# MeasureBlock.net
KiCad netlist of a schematic drawn in Altium Designer
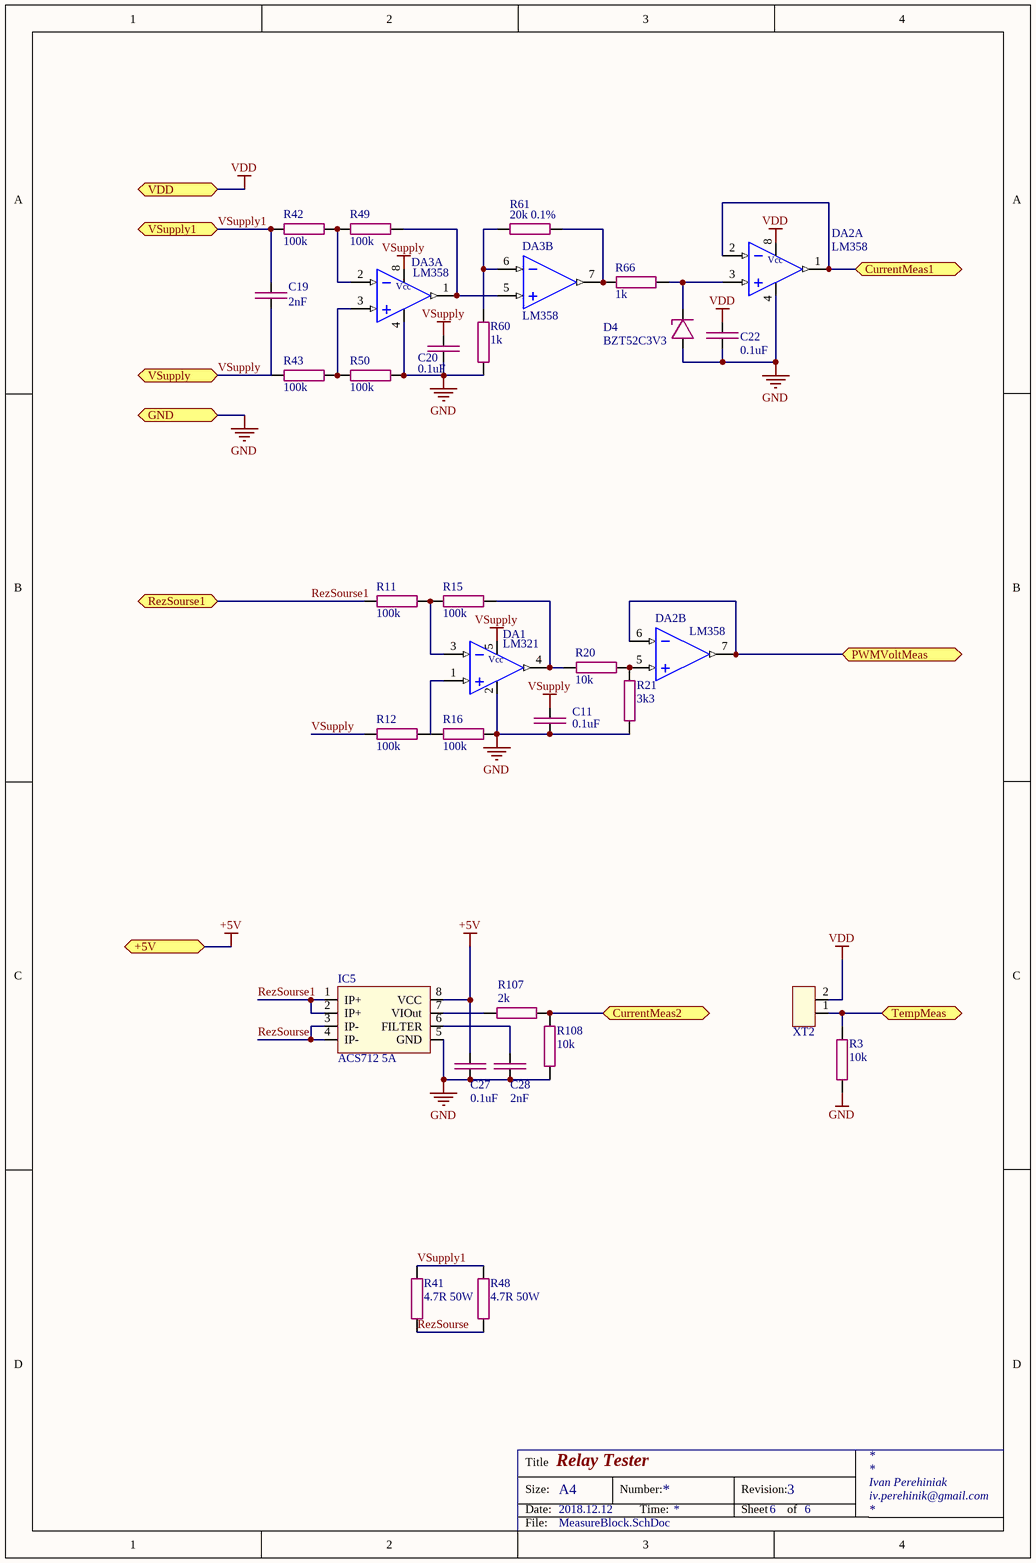
[diagram p0: MeasureBlock.SchDoc]

(export (version "E")
  (design (tool "Eeschema 10.0.6"))
  (components
    (comp (ref "C11")
      (value "0.1uF")
      (footprint "PcbLib:C0603")
      (description "CAP CER 0.1UF 50V X7R 0603")
      (fields (field (name "MANUFACTURER PART NUMBER") "GMK316F475ZG-T"))
      (libsource (lib "RCU") (part "GMK316F475ZG-T"))
    )
    (comp (ref "C19")
      (value "2nF")
      (footprint "PcbLib:C0603")
      (description "CAP CER 2000PF 50V X7R 0603")
      (fields (field (name "MANUFACTURER PART NUMBER") "CL10B202KB8NNNC"))
      (libsource (lib "RCU") (part "CL10B202KB8NNNC"))
    )
    (comp (ref "C20")
      (value "0.1uF")
      (footprint "PcbLib:C0603")
      (description "CAP CER 0.1UF 50V X7R 0603")
      (fields (field (name "MANUFACTURER PART NUMBER") "GMK316F475ZG-T"))
      (libsource (lib "RCU") (part "GMK316F475ZG-T"))
    )
    (comp (ref "C22")
      (value "0.1uF")
      (footprint "PcbLib:C0603")
      (description "CAP CER 0.1UF 50V X7R 0603")
      (fields (field (name "MANUFACTURER PART NUMBER") "GMK316F475ZG-T"))
      (libsource (lib "RCU") (part "GMK316F475ZG-T"))
    )
    (comp (ref "C27")
      (value "0.1uF")
      (footprint "PcbLib:C0603")
      (description "CAP CER 0.1UF 50V X7R 0603")
      (fields (field (name "MANUFACTURER PART NUMBER") "GMK316F475ZG-T"))
      (libsource (lib "RCU") (part "GMK316F475ZG-T"))
    )
    (comp (ref "C28")
      (value "2nF")
      (footprint "PcbLib:C0603")
      (description "CAP CER 2000PF 50V X7R 0603")
      (fields (field (name "MANUFACTURER PART NUMBER") "CL10B202KB8NNNC"))
      (libsource (lib "RCU") (part "CL10B202KB8NNNC"))
    )
    (comp (ref "D4")
      (value "BZT52C3V3")
      (footprint "PcbLib:SOD123")
      (description "Diode Zener Single 3.3V 6% 370mW 2-Pin SOD-123 T/R")
      (fields (field (name "MANUFACTURER PART NUMBER") "BZT52C3V3-7-F"))
      (libsource (lib "RCU") (part "BZT52C3V3-7-F"))
    )
    (comp (ref "DA1")
      (value "LM321")
      (footprint "PcbLib:SOT23-5")
      (description "IC OPAMP GP 1.3MHZ RRO SOT23-5")
      (fields (field (name "MANUFACTURER PART NUMBER") "LMV321ILT"))
      (libsource (lib "RCU") (part "LM321"))
    )
    (comp (ref "DA2")
      (value "LM358")
      (footprint "PcbLib:SOIC_N")
      (description "Dual IC OPAMP GP 1.1MHZ 8SO")
      (fields (field (name "MANUFACTURER PART NUMBER") "LM358DT"))
      (libsource (lib "RCU") (part "LM358DT"))
    )
    (comp (ref "DA3")
      (value "LM358")
      (footprint "PcbLib:SOIC_N")
      (description "Dual IC OPAMP GP 1.1MHZ 8SO")
      (fields (field (name "MANUFACTURER PART NUMBER") "LM358DT"))
      (libsource (lib "RCU") (part "LM358DT"))
    )
    (comp (ref "IC5")
      (value "ACS712 5A")
      (footprint "PcbLib:SOIC_N")
      (description "SENSOR CURRENT HALL 5A AC/DC")
      (fields (field (name "MANUFACTURER PART NUMBER") "ACS712ELCTR-05B-T"))
      (libsource (lib "RCU") (part "ACS712ELCTR-05B"))
    )
    (comp (ref "R3")
      (value "10k")
      (footprint "PcbLib:R0603")
      (description "RES SMD 10K OHM 1% 1/10W 0603")
      (fields (field (name "MANUFACTURER PART NUMBER") "CRCW060310K0FKTABC"))
      (libsource (lib "RCU") (part "CRCW060310K0FKTABC"))
    )
    (comp (ref "R11")
      (value "100k")
      (footprint "PcbLib:R0603")
      (description "RES SMD 100K OHM 5% 1/10W 0603")
      (fields (field (name "MANUFACTURER PART NUMBER") "ERJ-S03J104V"))
      (libsource (lib "RCU") (part "ERJ-S03J104V"))
    )
    (comp (ref "R12")
      (value "100k")
      (footprint "PcbLib:R0603")
      (description "RES SMD 100K OHM 5% 1/10W 0603")
      (fields (field (name "MANUFACTURER PART NUMBER") "ERJ-S03J104V"))
      (libsource (lib "RCU") (part "ERJ-S03J104V"))
    )
    (comp (ref "R15")
      (value "100k")
      (footprint "PcbLib:R0603")
      (description "RES SMD 100K OHM 5% 1/10W 0603")
      (fields (field (name "MANUFACTURER PART NUMBER") "ERJ-S03J104V"))
      (libsource (lib "RCU") (part "ERJ-S03J104V"))
    )
    (comp (ref "R16")
      (value "100k")
      (footprint "PcbLib:R0603")
      (description "RES SMD 100K OHM 5% 1/10W 0603")
      (fields (field (name "MANUFACTURER PART NUMBER") "ERJ-S03J104V"))
      (libsource (lib "RCU") (part "ERJ-S03J104V"))
    )
    (comp (ref "R20")
      (value "10k")
      (footprint "PcbLib:R0603")
      (description "RES SMD 10K OHM 1% 1/10W 0603")
      (fields (field (name "MANUFACTURER PART NUMBER") "CRCW060310K0FKTABC"))
      (libsource (lib "RCU") (part "CRCW060310K0FKTABC"))
    )
    (comp (ref "R21")
      (value "3k3")
      (footprint "PcbLib:R0603")
      (description "RES SMD 3.3K OHM 1% 1/10W 0603")
      (fields (field (name "MANUFACTURER PART NUMBER") "CRCW06033K30FKTABC"))
      (libsource (lib "RCU") (part "CRCW06033K30FKTABC"))
    )
    (comp (ref "R41")
      (value "4.7R 50W")
      (footprint "PcbLib:TO-220-2-hor")
      (description "RES 4.7 OHM 50W 5% AXIAL")
      (fields (field (name "MANUFACTURER PART NUMBER") "RTO050F4R700JTE3"))
      (libsource (lib "RCU") (part "RTO050F4R700JTE3"))
    )
    (comp (ref "R42")
      (value "100k")
      (footprint "PcbLib:R0603")
      (description "RES SMD 100K OHM 5% 1/10W 0603")
      (fields (field (name "MANUFACTURER PART NUMBER") "ERJ-S03J104V"))
      (libsource (lib "RCU") (part "ERJ-S03J104V"))
    )
    (comp (ref "R43")
      (value "100k")
      (footprint "PcbLib:R0603")
      (description "RES SMD 100K OHM 5% 1/10W 0603")
      (fields (field (name "MANUFACTURER PART NUMBER") "ERJ-S03J104V"))
      (libsource (lib "RCU") (part "ERJ-S03J104V"))
    )
    (comp (ref "R48")
      (value "4.7R 50W")
      (footprint "PcbLib:TO-220-2-hor")
      (description "RES 4.7 OHM 50W 5% AXIAL")
      (fields (field (name "MANUFACTURER PART NUMBER") "RTO050F4R700JTE3"))
      (libsource (lib "RCU") (part "RTO050F4R700JTE3"))
    )
    (comp (ref "R49")
      (value "100k")
      (footprint "PcbLib:R0603")
      (description "RES SMD 100K OHM 5% 1/10W 0603")
      (fields (field (name "MANUFACTURER PART NUMBER") "ERJ-S03J104V"))
      (libsource (lib "RCU") (part "ERJ-S03J104V"))
    )
    (comp (ref "R50")
      (value "100k")
      (footprint "PcbLib:R0603")
      (description "RES SMD 100K OHM 5% 1/10W 0603")
      (fields (field (name "MANUFACTURER PART NUMBER") "ERJ-S03J104V"))
      (libsource (lib "RCU") (part "ERJ-S03J104V"))
    )
    (comp (ref "R60")
      (value "1k")
      (footprint "PcbLib:R0603")
      (description "RES SMD 1K OHM 5% 1/10W 0603")
      (fields (field (name "MANUFACTURER PART NUMBER") "ERJ-3GEYJ102V"))
      (libsource (lib "RCU") (part "ERJ-3GEYJ102V"))
    )
    (comp (ref "R61")
      (value "20k 0.1%")
      (footprint "PcbLib:R0603")
      (description "RES SMD 20K OHM 0.1% 1/10W 0603")
      (fields (field (name "MANUFACTURER PART NUMBER") "ERA-3AEB203V"))
      (libsource (lib "RCU") (part "ERA-3AEB203V"))
    )
    (comp (ref "R66")
      (value "1k")
      (footprint "PcbLib:R0603")
      (description "RES SMD 1K OHM 5% 1/10W 0603")
      (fields (field (name "MANUFACTURER PART NUMBER") "ERJ-3GEYJ102V"))
      (libsource (lib "RCU") (part "ERJ-3GEYJ102V"))
    )
    (comp (ref "R107")
      (value "2k")
      (footprint "PcbLib:R0603")
      (description "RES SMD 2K OHM 1% 1/10W 0603")
      (fields (field (name "MANUFACTURER PART NUMBER") "CRCW06032K00FKTABC"))
      (libsource (lib "RCU") (part "CRCW06032K00FKTABC"))
    )
    (comp (ref "R108")
      (value "10k")
      (footprint "PcbLib:R0603")
      (description "RES SMD 10K OHM 1% 1/10W 0603")
      (fields (field (name "MANUFACTURER PART NUMBER") "CRCW060310K0FKTABC"))
      (libsource (lib "RCU") (part "CRCW060310K0FKTABC"))
    )
    (comp (ref "XT2")
      (value "PLS-2")
      (footprint "PcbLib:PLS-2")
      (description "SIL VERTICAL PC TAIL PIN HEADER")
      (fields (field (name "MANUFACTURER PART NUMBER") "M20-9990246"))
      (libsource (lib "RCU") (part "PLS-2"))
    )
  )
  (nets
    (net (code "1") (name "+5V") (class "Default")
      (node (ref "C27") (pin "2") (pinfunction "2_2") (pintype "passive"))
      (node (ref "IC5") (pin "8") (pinfunction "VCC_8") (pintype "passive"))
    )
    (net (code "2") (name "/CurrentMeas1") (class "Default")
      (node (ref "DA2") (pin "1") (pinfunction "OUT1_1") (pintype "output"))
      (node (ref "DA2") (pin "2") (pinfunction "IN1-_2") (pintype "input"))
    )
    (net (code "3") (name "/CurrentMeas2") (class "Default")
      (node (ref "R107") (pin "2") (pinfunction "2_2") (pintype "passive"))
      (node (ref "R108") (pin "2") (pinfunction "2_2") (pintype "passive"))
    )
    (net (code "4") (name "/PWMVoltMeas") (class "Default")
      (node (ref "DA2") (pin "6") (pinfunction "IN2-_6") (pintype "input"))
      (node (ref "DA2") (pin "7") (pinfunction "OUT2_7") (pintype "output"))
    )
    (net (code "5") (name "/RezSourse") (class "Default")
      (node (ref "IC5") (pin "3") (pinfunction "IP-_3") (pintype "passive"))
      (node (ref "IC5") (pin "4") (pinfunction "IP-_4") (pintype "passive"))
      (node (ref "R41") (pin "2") (pinfunction "2_2") (pintype "passive"))
      (node (ref "R48") (pin "1") (pinfunction "1_1") (pintype "passive"))
    )
    (net (code "6") (name "/RezSourse1") (class "Default")
      (node (ref "IC5") (pin "1") (pinfunction "IP+_1") (pintype "passive"))
      (node (ref "IC5") (pin "2") (pinfunction "IP+_2") (pintype "passive"))
      (node (ref "R11") (pin "1") (pinfunction "1_1") (pintype "passive"))
    )
    (net (code "7") (name "/TempMeas") (class "Default")
      (node (ref "R3") (pin "2") (pinfunction "2_2") (pintype "passive"))
      (node (ref "XT2") (pin "1") (pintype "passive"))
    )
    (net (code "8") (name "/VSupply1") (class "Default")
      (node (ref "C19") (pin "2") (pinfunction "2_2") (pintype "passive"))
      (node (ref "R41") (pin "1") (pinfunction "1_1") (pintype "passive"))
      (node (ref "R42") (pin "1") (pinfunction "1_1") (pintype "passive"))
      (node (ref "R48") (pin "2") (pinfunction "2_2") (pintype "passive"))
    )
    (net (code "9") (name "GND") (class "Default")
      (node (ref "C11") (pin "1") (pinfunction "1_1") (pintype "passive"))
      (node (ref "C20") (pin "1") (pinfunction "1_1") (pintype "passive"))
      (node (ref "C22") (pin "1") (pinfunction "1_1") (pintype "passive"))
      (node (ref "C27") (pin "1") (pinfunction "1_1") (pintype "passive"))
      (node (ref "C28") (pin "1") (pinfunction "1_1") (pintype "passive"))
      (node (ref "D4") (pin "1") (pinfunction "Anode_1") (pintype "passive"))
      (node (ref "DA1") (pin "2") (pinfunction "GND_2") (pintype "passive"))
      (node (ref "DA2") (pin "4") (pinfunction "GND_4") (pintype "passive"))
      (node (ref "DA3") (pin "4") (pinfunction "GND_4") (pintype "passive"))
      (node (ref "IC5") (pin "5") (pinfunction "GND_5") (pintype "passive"))
      (node (ref "R108") (pin "1") (pinfunction "1_1") (pintype "passive"))
      (node (ref "R16") (pin "2") (pinfunction "2_2") (pintype "passive"))
      (node (ref "R21") (pin "1") (pinfunction "1_1") (pintype "passive"))
      (node (ref "R3") (pin "1") (pinfunction "1_1") (pintype "passive"))
      (node (ref "R50") (pin "2") (pinfunction "2_2") (pintype "passive"))
      (node (ref "R60") (pin "1") (pinfunction "1_1") (pintype "passive"))
    )
    (net (code "10") (name "Net-(D4-Cathode)") (class "Default")
      (node (ref "D4") (pin "2") (pinfunction "Cathode_2") (pintype "passive"))
      (node (ref "DA2") (pin "3") (pinfunction "IN1+_3") (pintype "input"))
      (node (ref "R66") (pin "2") (pinfunction "2_2") (pintype "passive"))
    )
    (net (code "11") (name "Net-(DA1-IN1+)") (class "Default")
      (node (ref "DA1") (pin "1") (pinfunction "IN1+_1") (pintype "input"))
      (node (ref "R12") (pin "2") (pinfunction "2_2") (pintype "passive"))
      (node (ref "R16") (pin "1") (pinfunction "1_1") (pintype "passive"))
    )
    (net (code "12") (name "Net-(DA1-IN1-)") (class "Default")
      (node (ref "DA1") (pin "3") (pinfunction "IN1-_3") (pintype "input"))
      (node (ref "R11") (pin "2") (pinfunction "2_2") (pintype "passive"))
      (node (ref "R15") (pin "1") (pinfunction "1_1") (pintype "passive"))
    )
    (net (code "13") (name "Net-(DA1-OUT1)") (class "Default")
      (node (ref "DA1") (pin "4") (pinfunction "OUT1_4") (pintype "output"))
      (node (ref "R15") (pin "2") (pinfunction "2_2") (pintype "passive"))
      (node (ref "R20") (pin "2") (pinfunction "2_2") (pintype "passive"))
    )
    (net (code "14") (name "Net-(DA2B-IN2+)") (class "Default")
      (node (ref "DA2") (pin "5") (pinfunction "IN2+_5") (pintype "input"))
      (node (ref "R20") (pin "1") (pinfunction "1_1") (pintype "passive"))
      (node (ref "R21") (pin "2") (pinfunction "2_2") (pintype "passive"))
    )
    (net (code "15") (name "Net-(DA3A-IN1+)") (class "Default")
      (node (ref "DA3") (pin "3") (pinfunction "IN1+_3") (pintype "input"))
      (node (ref "R43") (pin "2") (pinfunction "2_2") (pintype "passive"))
      (node (ref "R50") (pin "1") (pinfunction "1_1") (pintype "passive"))
    )
    (net (code "16") (name "Net-(DA3A-IN1-)") (class "Default")
      (node (ref "DA3") (pin "2") (pinfunction "IN1-_2") (pintype "input"))
      (node (ref "R42") (pin "2") (pinfunction "2_2") (pintype "passive"))
      (node (ref "R49") (pin "1") (pinfunction "1_1") (pintype "passive"))
    )
    (net (code "17") (name "Net-(DA3A-OUT1)") (class "Default")
      (node (ref "DA3") (pin "1") (pinfunction "OUT1_1") (pintype "output"))
      (node (ref "DA3") (pin "5") (pinfunction "IN2+_5") (pintype "input"))
      (node (ref "R49") (pin "2") (pinfunction "2_2") (pintype "passive"))
    )
    (net (code "18") (name "Net-(DA3B-IN2-)") (class "Default")
      (node (ref "DA3") (pin "6") (pinfunction "IN2-_6") (pintype "input"))
      (node (ref "R60") (pin "2") (pinfunction "2_2") (pintype "passive"))
      (node (ref "R61") (pin "1") (pinfunction "1_1") (pintype "passive"))
    )
    (net (code "19") (name "Net-(DA3B-OUT2)") (class "Default")
      (node (ref "DA3") (pin "7") (pinfunction "OUT2_7") (pintype "output"))
      (node (ref "R61") (pin "2") (pinfunction "2_2") (pintype "passive"))
      (node (ref "R66") (pin "1") (pinfunction "1_1") (pintype "passive"))
    )
    (net (code "20") (name "Net-(IC5-FILTER)") (class "Default")
      (node (ref "C28") (pin "2") (pinfunction "2_2") (pintype "passive"))
      (node (ref "IC5") (pin "6") (pinfunction "FILTER_6") (pintype "passive"))
    )
    (net (code "21") (name "Net-(IC5-VIOut)") (class "Default")
      (node (ref "IC5") (pin "7") (pinfunction "VIOut_7") (pintype "passive"))
      (node (ref "R107") (pin "1") (pinfunction "1_1") (pintype "passive"))
    )
    (net (code "22") (name "VDD") (class "Default")
      (node (ref "C22") (pin "2") (pinfunction "2_2") (pintype "passive"))
      (node (ref "DA2") (pin "8") (pinfunction "Vcc_8") (pintype "passive"))
      (node (ref "XT2") (pin "2") (pintype "passive"))
    )
    (net (code "23") (name "VSupply") (class "Default")
      (node (ref "C11") (pin "2") (pinfunction "2_2") (pintype "passive"))
      (node (ref "C19") (pin "1") (pinfunction "1_1") (pintype "passive"))
      (node (ref "C20") (pin "2") (pinfunction "2_2") (pintype "passive"))
      (node (ref "DA1") (pin "5") (pinfunction "Vcc_5") (pintype "passive"))
      (node (ref "DA3") (pin "8") (pinfunction "Vcc_8") (pintype "passive"))
      (node (ref "R12") (pin "1") (pinfunction "1_1") (pintype "passive"))
      (node (ref "R43") (pin "1") (pinfunction "1_1") (pintype "passive"))
    )
  )
)
